# Mainboard33WithHeadersv5.net
KiCad netlist of a schematic drawn in EAGLE
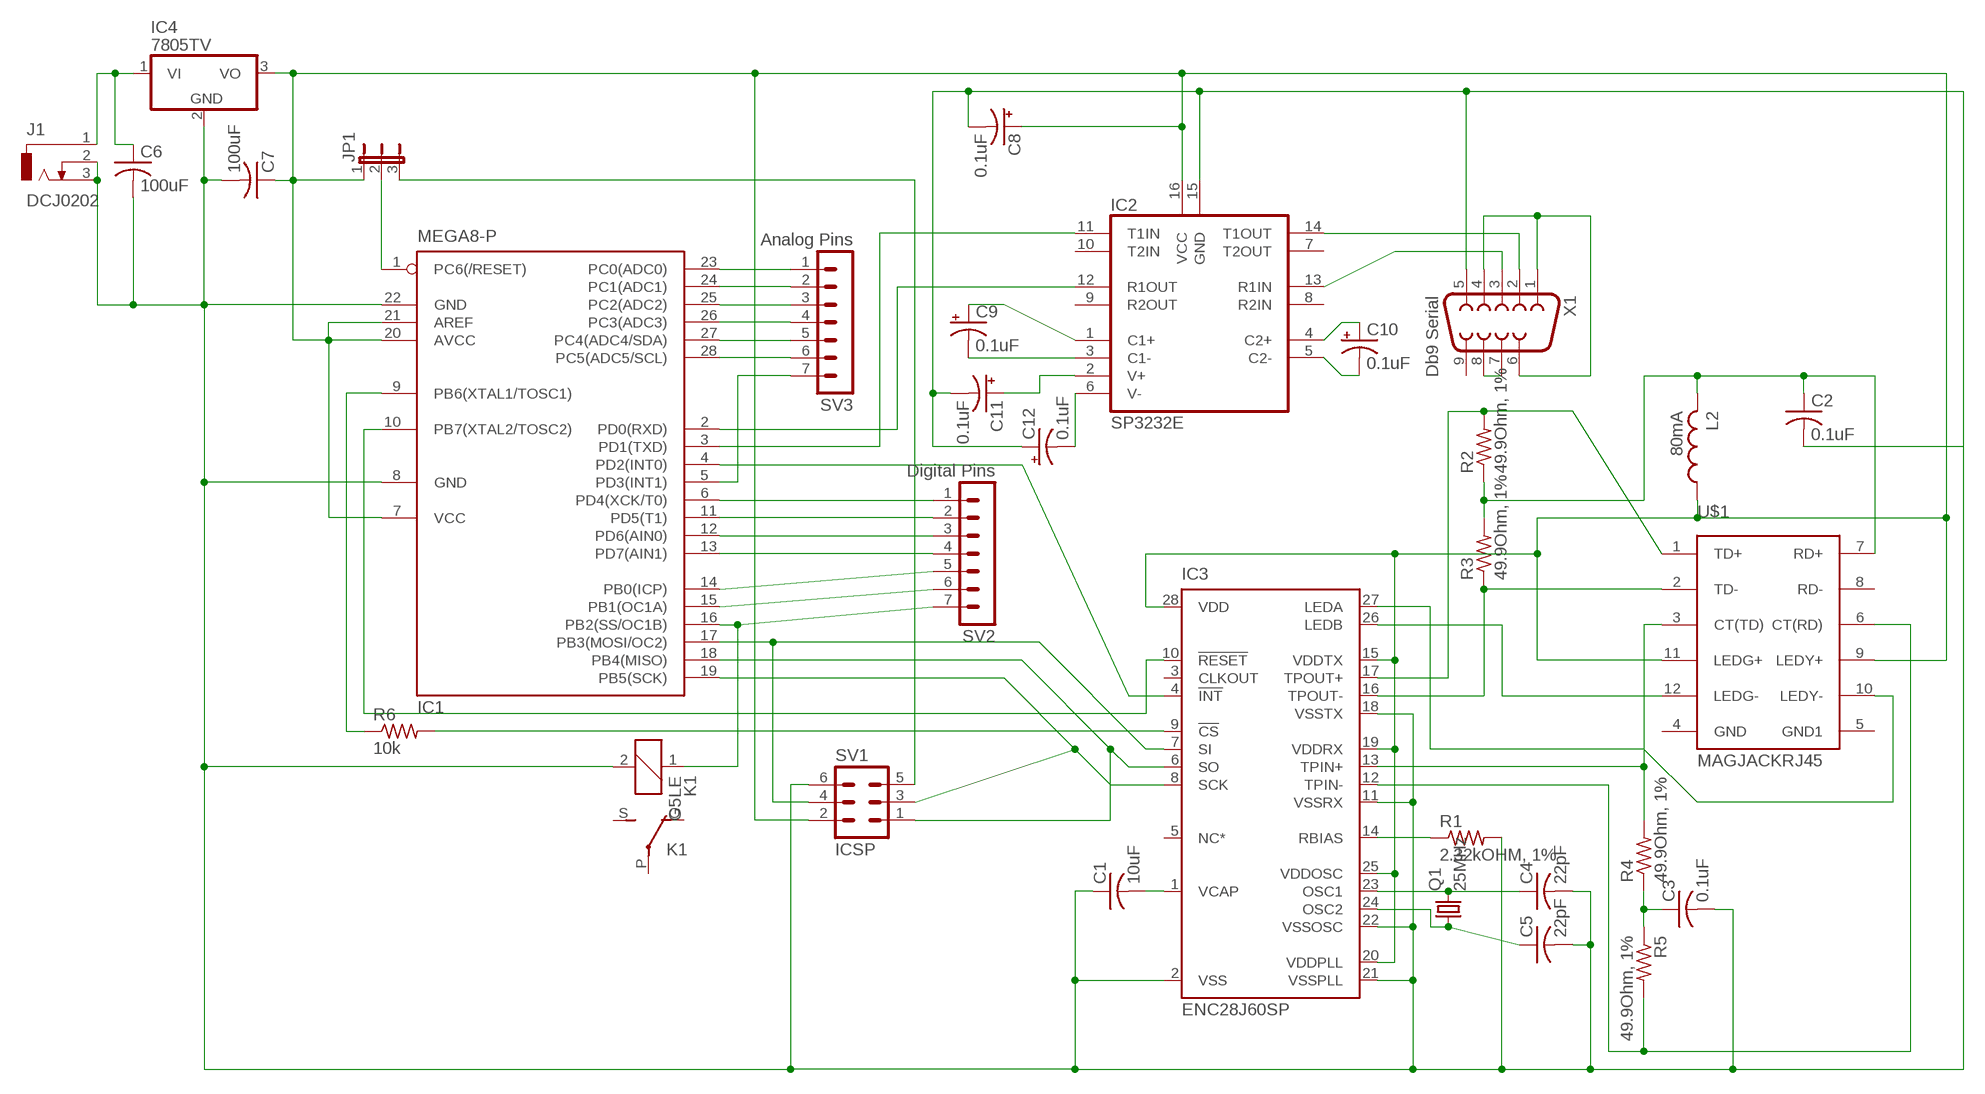
[diagram p0: schematic, sheet 1]

(export (version "E")
  (design (tool "Eeschema 10.0.6"))
  (components
    (comp (ref "C1")
      (value "10uF")
      (footprint "eagle-import:C050-024X044")
      (libsource (lib "eagle-import") (part "C-US050-024X044"))
    )
    (comp (ref "C2")
      (value "0.1uF")
      (footprint "eagle-import:C050-024X044")
      (libsource (lib "eagle-import") (part "C-US050-024X044"))
    )
    (comp (ref "C3")
      (value "0.1uF")
      (footprint "eagle-import:C050-024X044")
      (libsource (lib "eagle-import") (part "C-US050-024X044"))
    )
    (comp (ref "C4")
      (value "22pF")
      (footprint "eagle-import:C050-024X044")
      (libsource (lib "eagle-import") (part "C-US050-024X044"))
    )
    (comp (ref "C5")
      (value "22pF")
      (footprint "eagle-import:C050-024X044")
      (libsource (lib "eagle-import") (part "C-US050-024X044"))
    )
    (comp (ref "C6")
      (value "100uF")
      (footprint "eagle-import:C050-030X075")
      (libsource (lib "eagle-import") (part "C-US050-030X075"))
    )
    (comp (ref "C7")
      (value "100uF")
      (footprint "eagle-import:C050-035X075")
      (libsource (lib "eagle-import") (part "C-US050-035X075"))
    )
    (comp (ref "C8")
      (value "0.1uF")
      (footprint "eagle-import:E1,8-4")
      (libsource (lib "eagle-import") (part "CPOL-USE1.8-4"))
    )
    (comp (ref "C9")
      (value "0.1uF")
      (footprint "eagle-import:E1,8-4")
      (libsource (lib "eagle-import") (part "CPOL-USE1.8-4"))
    )
    (comp (ref "C10")
      (value "0.1uF")
      (footprint "eagle-import:E1,8-4")
      (libsource (lib "eagle-import") (part "CPOL-USE1.8-4"))
    )
    (comp (ref "C11")
      (value "0.1uF")
      (footprint "eagle-import:E1,8-4")
      (libsource (lib "eagle-import") (part "CPOL-USE1.8-4"))
    )
    (comp (ref "C12")
      (value "0.1uF")
      (footprint "eagle-import:E1,8-4")
      (libsource (lib "eagle-import") (part "CPOL-USE1.8-4"))
    )
    (comp (ref "IC1")
      (value "MEGA8-P")
      (footprint "eagle-import:DIL28-3")
      (libsource (lib "eagle-import") (part "MEGA8-P"))
    )
    (comp (ref "IC2")
      (value "SP3232E")
      (footprint "eagle-import:DIL16")
      (libsource (lib "eagle-import") (part "SP3232ESP3232E"))
    )
    (comp (ref "IC3")
      (value "ENC28J60SP")
      (footprint "eagle-import:DIL28-3")
      (fields (field (name "MF") "MICROCHIP") (field (name "MPN") "ENC28J60/SP"))
      (libsource (lib "eagle-import") (part "ENC28J60SP"))
    )
    (comp (ref "IC4")
      (value "7805TV")
      (footprint "eagle-import:TO220V")
      (libsource (lib "eagle-import") (part "78TV05"))
    )
    (comp (ref "J1")
      (value "DCJ0202")
      (footprint "eagle-import:DCJ0202")
      (libsource (lib "eagle-import") (part "DCJ0202"))
    )
    (comp (ref "JP1")
      (value "JP2E")
      (footprint "eagle-import:JP2")
      (libsource (lib "eagle-import") (part "JP2E"))
    )
    (comp (ref "K1")
      (value "G5LE")
      (footprint "eagle-import:G5LE")
      (libsource (lib "eagle-import") (part "G5LE"))
    )
    (comp (ref "L2")
      (value "80mA")
      (footprint "eagle-import:0207_10")
      (libsource (lib "eagle-import") (part "L-US0207/10"))
    )
    (comp (ref "Q1")
      (value "25MHz")
      (footprint "eagle-import:HC49_S")
      (fields (field (name "OC_FARNELL") "1667008"))
      (libsource (lib "eagle-import") (part "CRYSTALHC49S"))
    )
    (comp (ref "R1")
      (value "2.32kOHM, 1%")
      (footprint "eagle-import:0204_5")
      (libsource (lib "eagle-import") (part "resistor_R-US_0204/5"))
    )
    (comp (ref "R2")
      (value "49.9Ohm, 1%")
      (footprint "eagle-import:0204_5")
      (libsource (lib "eagle-import") (part "resistor_R-US_0204/5"))
    )
    (comp (ref "R3")
      (value "49.9Ohm, 1%")
      (footprint "eagle-import:0204_5")
      (libsource (lib "eagle-import") (part "resistor_R-US_0204/5"))
    )
    (comp (ref "R4")
      (value "49.9Ohm, 1%")
      (footprint "eagle-import:0204_5")
      (libsource (lib "eagle-import") (part "resistor_R-US_0204/5"))
    )
    (comp (ref "R5")
      (value "49.9Ohm, 1%")
      (footprint "eagle-import:0204_5")
      (libsource (lib "eagle-import") (part "resistor_R-US_0204/5"))
    )
    (comp (ref "R6")
      (value "10k")
      (footprint "eagle-import:0204_5")
      (libsource (lib "eagle-import") (part "R-US_0204/5"))
    )
    (comp (ref "SV1")
      (value "ICSP")
      (footprint "eagle-import:MA03-2")
      (libsource (lib "eagle-import") (part "MA03-2"))
    )
    (comp (ref "SV2")
      (value "Digital Pins")
      (footprint "eagle-import:MA07-1")
      (libsource (lib "eagle-import") (part "MA07-1"))
    )
    (comp (ref "SV3")
      (value "Analog Pins")
      (footprint "eagle-import:MA07-1")
      (libsource (lib "eagle-import") (part "MA07-1"))
    )
    (comp (ref "U$1")
      (value "MAGJACKRJ45")
      (footprint "eagle-import:MAGJACK")
      (libsource (lib "eagle-import") (part "MAGJACKRJ45"))
    )
    (comp (ref "X1")
      (value "Db9 Serial")
      (footprint "eagle-import:F09H")
      (libsource (lib "eagle-import") (part "F09H"))
    )
  )
  (nets
    (net (code "1") (name "/GND") (class "Default")
      (node (ref "U$1") (pin "4") (pinfunction "GND_4") (pintype "power_in"))
    )
    (net (code "2") (name "/GND1") (class "Default")
      (node (ref "U$1") (pin "5") (pinfunction "GND1_5") (pintype "power_in"))
    )
    (net (code "3") (name "Net-(C3-Pad1)") (class "Default")
      (node (ref "C3") (pin "1") (pinfunction "1_1") (pintype "passive"))
      (node (ref "R4") (pin "1") (pinfunction "1_1") (pintype "passive"))
      (node (ref "R5") (pin "1") (pinfunction "1_1") (pintype "passive"))
    )
    (net (code "4") (name "Net-(IC1-AREF)") (class "Default")
      (node (ref "C7") (pin "1") (pinfunction "1_1") (pintype "passive"))
      (node (ref "C8") (pin "+") (pinfunction "+_+") (pintype "passive"))
      (node (ref "IC1") (pin "20") (pinfunction "AVCC_20") (pintype "power_in"))
      (node (ref "IC1") (pin "21") (pinfunction "AREF_21") (pintype "passive"))
      (node (ref "IC1") (pin "7") (pinfunction "VCC_7") (pintype "power_in"))
      (node (ref "IC2") (pin "16") (pinfunction "VCC_16") (pintype "power_in"))
      (node (ref "IC3") (pin "15") (pinfunction "VDDTX_15") (pintype "input"))
      (node (ref "IC3") (pin "19") (pinfunction "VDDRX_19") (pintype "input"))
      (node (ref "IC3") (pin "20") (pinfunction "VDDPLL_20") (pintype "input"))
      (node (ref "IC3") (pin "25") (pinfunction "VDDOSC_25") (pintype "input"))
      (node (ref "IC3") (pin "28") (pinfunction "VDD_28") (pintype "input"))
      (node (ref "IC4") (pin "3") (pinfunction "VO_3") (pintype "passive"))
      (node (ref "JP1") (pin "1") (pinfunction "1_1") (pintype "passive"))
      (node (ref "L2") (pin "1") (pinfunction "1_1") (pintype "passive"))
      (node (ref "SV1") (pin "2") (pinfunction "2_2") (pintype "passive"))
      (node (ref "U$1") (pin "11") (pinfunction "LEDG+_11") (pintype "bidirectional"))
      (node (ref "U$1") (pin "9") (pinfunction "LEDY+_9") (pintype "bidirectional"))
    )
    (net (code "5") (name "Net-(IC1-PB0(ICP))") (class "Default")
      (node (ref "IC1") (pin "14") (pinfunction "PB0(ICP)_14") (pintype "bidirectional"))
      (node (ref "SV2") (pin "5") (pinfunction "5_5") (pintype "passive"))
    )
    (net (code "6") (name "Net-(IC1-PB1(OC1A))") (class "Default")
      (node (ref "IC1") (pin "15") (pinfunction "PB1(OC1A)_15") (pintype "bidirectional"))
      (node (ref "SV2") (pin "6") (pinfunction "6_6") (pintype "passive"))
    )
    (net (code "7") (name "Net-(IC1-PB2(SS{slash}OC1B))") (class "Default")
      (node (ref "IC1") (pin "16") (pinfunction "PB2(SS/OC1B)_16") (pintype "bidirectional"))
      (node (ref "K1") (pin "1") (pinfunction "1_1") (pintype "passive"))
      (node (ref "SV2") (pin "7") (pinfunction "7_7") (pintype "passive"))
    )
    (net (code "8") (name "Net-(IC1-PB3(MOSI{slash}OC2))") (class "Default")
      (node (ref "IC1") (pin "17") (pinfunction "PB3(MOSI/OC2)_17") (pintype "bidirectional"))
      (node (ref "IC3") (pin "7") (pinfunction "SI_7") (pintype "input"))
      (node (ref "SV1") (pin "4") (pinfunction "4_4") (pintype "passive"))
    )
    (net (code "9") (name "Net-(IC1-PB4(MISO))") (class "Default")
      (node (ref "IC1") (pin "18") (pinfunction "PB4(MISO)_18") (pintype "bidirectional"))
      (node (ref "IC3") (pin "6") (pinfunction "SO_6") (pintype "output"))
      (node (ref "SV1") (pin "1") (pinfunction "1_1") (pintype "passive"))
    )
    (net (code "10") (name "Net-(IC1-PB5(SCK))") (class "Default")
      (node (ref "IC1") (pin "19") (pinfunction "PB5(SCK)_19") (pintype "bidirectional"))
      (node (ref "IC3") (pin "8") (pinfunction "SCK_8") (pintype "input"))
      (node (ref "SV1") (pin "3") (pinfunction "3_3") (pintype "passive"))
    )
    (net (code "11") (name "Net-(IC1-PB6(XTAL1{slash}TOSC1))") (class "Default")
      (node (ref "IC1") (pin "9") (pinfunction "PB6(XTAL1/TOSC1)_9") (pintype "bidirectional"))
      (node (ref "R6") (pin "1") (pinfunction "1_1") (pintype "passive"))
    )
    (net (code "12") (name "Net-(IC1-PB7(XTAL2{slash}TOSC2))") (class "Default")
      (node (ref "IC1") (pin "10") (pinfunction "PB7(XTAL2/TOSC2)_10") (pintype "bidirectional"))
      (node (ref "IC3") (pin "10") (pinfunction "~{RESET}_10") (pintype "input"))
    )
    (net (code "13") (name "Net-(IC1-PC0(ADC0))") (class "Default")
      (node (ref "IC1") (pin "23") (pinfunction "PC0(ADC0)_23") (pintype "bidirectional"))
      (node (ref "SV3") (pin "1") (pinfunction "1_1") (pintype "passive"))
    )
    (net (code "14") (name "Net-(IC1-PC1(ADC1))") (class "Default")
      (node (ref "IC1") (pin "24") (pinfunction "PC1(ADC1)_24") (pintype "bidirectional"))
      (node (ref "SV3") (pin "2") (pinfunction "2_2") (pintype "passive"))
    )
    (net (code "15") (name "Net-(IC1-PC2(ADC2))") (class "Default")
      (node (ref "IC1") (pin "25") (pinfunction "PC2(ADC2)_25") (pintype "bidirectional"))
      (node (ref "SV3") (pin "3") (pinfunction "3_3") (pintype "passive"))
    )
    (net (code "16") (name "Net-(IC1-PC3(ADC3))") (class "Default")
      (node (ref "IC1") (pin "26") (pinfunction "PC3(ADC3)_26") (pintype "bidirectional"))
      (node (ref "SV3") (pin "4") (pinfunction "4_4") (pintype "passive"))
    )
    (net (code "17") (name "Net-(IC1-PC4(ADC4{slash}SDA))") (class "Default")
      (node (ref "IC1") (pin "27") (pinfunction "PC4(ADC4/SDA)_27") (pintype "bidirectional"))
      (node (ref "SV3") (pin "5") (pinfunction "5_5") (pintype "passive"))
    )
    (net (code "18") (name "Net-(IC1-PC5(ADC5{slash}SCL))") (class "Default")
      (node (ref "IC1") (pin "28") (pinfunction "PC5(ADC5/SCL)_28") (pintype "bidirectional"))
      (node (ref "SV3") (pin "6") (pinfunction "6_6") (pintype "passive"))
    )
    (net (code "19") (name "Net-(IC1-PC6({slash}RESET))") (class "Default")
      (node (ref "IC1") (pin "1") (pinfunction "PC6(/RESET)_1") (pintype "bidirectional"))
      (node (ref "JP1") (pin "2") (pinfunction "2_2") (pintype "passive"))
    )
    (net (code "20") (name "Net-(IC1-PD0(RXD))") (class "Default")
      (node (ref "IC1") (pin "2") (pinfunction "PD0(RXD)_2") (pintype "bidirectional"))
      (node (ref "IC2") (pin "12") (pinfunction "R1OUT_12") (pintype "output"))
    )
    (net (code "21") (name "Net-(IC1-PD1(TXD))") (class "Default")
      (node (ref "IC1") (pin "3") (pinfunction "PD1(TXD)_3") (pintype "bidirectional"))
      (node (ref "IC2") (pin "11") (pinfunction "T1IN_11") (pintype "input"))
    )
    (net (code "22") (name "Net-(IC1-PD2(INT0))") (class "Default")
      (node (ref "IC1") (pin "4") (pinfunction "PD2(INT0)_4") (pintype "bidirectional"))
      (node (ref "IC3") (pin "4") (pinfunction "~{INT}_4") (pintype "output"))
    )
    (net (code "23") (name "Net-(IC1-PD3(INT1))") (class "Default")
      (node (ref "IC1") (pin "5") (pinfunction "PD3(INT1)_5") (pintype "bidirectional"))
      (node (ref "SV3") (pin "7") (pinfunction "7_7") (pintype "passive"))
    )
    (net (code "24") (name "Net-(IC1-PD4(XCK{slash}T0))") (class "Default")
      (node (ref "IC1") (pin "6") (pinfunction "PD4(XCK/T0)_6") (pintype "bidirectional"))
      (node (ref "SV2") (pin "1") (pinfunction "1_1") (pintype "passive"))
    )
    (net (code "25") (name "Net-(IC1-PD5(T1))") (class "Default")
      (node (ref "IC1") (pin "11") (pinfunction "PD5(T1)_11") (pintype "bidirectional"))
      (node (ref "SV2") (pin "2") (pinfunction "2_2") (pintype "passive"))
    )
    (net (code "26") (name "Net-(IC1-PD6(AIN0))") (class "Default")
      (node (ref "IC1") (pin "12") (pinfunction "PD6(AIN0)_12") (pintype "bidirectional"))
      (node (ref "SV2") (pin "3") (pinfunction "3_3") (pintype "passive"))
    )
    (net (code "27") (name "Net-(IC1-PD7(AIN1))") (class "Default")
      (node (ref "IC1") (pin "13") (pinfunction "PD7(AIN1)_13") (pintype "bidirectional"))
      (node (ref "SV2") (pin "4") (pinfunction "4_4") (pintype "passive"))
    )
    (net (code "28") (name "Net-(IC2-C1+)") (class "Default")
      (node (ref "C9") (pin "+") (pinfunction "+_+") (pintype "passive"))
      (node (ref "IC2") (pin "1") (pinfunction "C1+_1") (pintype "input"))
    )
    (net (code "29") (name "Net-(IC2-C1-)") (class "Default")
      (node (ref "C9") (pin "-") (pinfunction "-_-") (pintype "passive"))
      (node (ref "IC2") (pin "3") (pinfunction "C1-_3") (pintype "input"))
    )
    (net (code "30") (name "Net-(IC2-C2+)") (class "Default")
      (node (ref "C10") (pin "+") (pinfunction "+_+") (pintype "passive"))
      (node (ref "IC2") (pin "4") (pinfunction "C2+_4") (pintype "input"))
    )
    (net (code "31") (name "Net-(IC2-C2-)") (class "Default")
      (node (ref "C10") (pin "-") (pinfunction "-_-") (pintype "passive"))
      (node (ref "IC2") (pin "5") (pinfunction "C2-_5") (pintype "input"))
    )
    (net (code "32") (name "Net-(IC2-GND)") (class "Default")
      (node (ref "C1") (pin "1") (pinfunction "1_1") (pintype "passive"))
      (node (ref "C11") (pin "-") (pinfunction "-_-") (pintype "passive"))
      (node (ref "C12") (pin "+") (pinfunction "+_+") (pintype "passive"))
      (node (ref "C2") (pin "2") (pinfunction "2_2") (pintype "passive"))
      (node (ref "C3") (pin "2") (pinfunction "2_2") (pintype "passive"))
      (node (ref "C4") (pin "2") (pinfunction "2_2") (pintype "passive"))
      (node (ref "C5") (pin "2") (pinfunction "2_2") (pintype "passive"))
      (node (ref "C6") (pin "2") (pinfunction "2_2") (pintype "passive"))
      (node (ref "C7") (pin "2") (pinfunction "2_2") (pintype "passive"))
      (node (ref "C8") (pin "-") (pinfunction "-_-") (pintype "passive"))
      (node (ref "IC1") (pin "22") (pinfunction "GND_22") (pintype "power_in"))
      (node (ref "IC1") (pin "8") (pinfunction "GND_8") (pintype "power_in"))
      (node (ref "IC2") (pin "15") (pinfunction "GND_15") (pintype "power_in"))
      (node (ref "IC3") (pin "11") (pinfunction "VSSRX_11") (pintype "input"))
      (node (ref "IC3") (pin "18") (pinfunction "VSSTX_18") (pintype "input"))
      (node (ref "IC3") (pin "2") (pinfunction "VSS_2") (pintype "input"))
      (node (ref "IC3") (pin "21") (pinfunction "VSSPLL_21") (pintype "input"))
      (node (ref "IC3") (pin "22") (pinfunction "VSSOSC_22") (pintype "input"))
      (node (ref "IC4") (pin "2") (pinfunction "GND_2") (pintype "passive"))
      (node (ref "J1") (pin "2") (pinfunction "2_2") (pintype "passive"))
      (node (ref "J1") (pin "3") (pinfunction "3_3") (pintype "passive"))
      (node (ref "K1") (pin "2") (pinfunction "2_2") (pintype "passive"))
      (node (ref "R1") (pin "2") (pinfunction "2_2") (pintype "passive"))
      (node (ref "SV1") (pin "6") (pinfunction "6_6") (pintype "passive"))
      (node (ref "X1") (pin "5") (pinfunction "5_5") (pintype "passive"))
    )
    (net (code "33") (name "Net-(IC2-R1IN)") (class "Default")
      (node (ref "IC2") (pin "13") (pinfunction "R1IN_13") (pintype "input"))
      (node (ref "X1") (pin "3") (pinfunction "3_3") (pintype "passive"))
    )
    (net (code "34") (name "Net-(IC2-T1OUT)") (class "Default")
      (node (ref "IC2") (pin "14") (pinfunction "T1OUT_14") (pintype "output"))
      (node (ref "X1") (pin "2") (pinfunction "2_2") (pintype "passive"))
    )
    (net (code "35") (name "Net-(IC2-V+)") (class "Default")
      (node (ref "C11") (pin "+") (pinfunction "+_+") (pintype "passive"))
      (node (ref "IC2") (pin "2") (pinfunction "V+_2") (pintype "input"))
    )
    (net (code "36") (name "Net-(IC2-V-)") (class "Default")
      (node (ref "C12") (pin "-") (pinfunction "-_-") (pintype "passive"))
      (node (ref "IC2") (pin "6") (pinfunction "V-_6") (pintype "input"))
    )
    (net (code "37") (name "Net-(IC3-LEDA)") (class "Default")
      (node (ref "IC3") (pin "27") (pinfunction "LEDA_27") (pintype "output"))
      (node (ref "U$1") (pin "10") (pinfunction "LEDY-_10") (pintype "bidirectional"))
    )
    (net (code "38") (name "Net-(IC3-LEDB)") (class "Default")
      (node (ref "IC3") (pin "26") (pinfunction "LEDB_26") (pintype "output"))
      (node (ref "U$1") (pin "12") (pinfunction "LEDG-_12") (pintype "bidirectional"))
    )
    (net (code "39") (name "Net-(IC3-OSC1)") (class "Default")
      (node (ref "C4") (pin "1") (pinfunction "1_1") (pintype "passive"))
      (node (ref "IC3") (pin "23") (pinfunction "OSC1_23") (pintype "input"))
      (node (ref "Q1") (pin "2") (pinfunction "2_2") (pintype "passive"))
    )
    (net (code "40") (name "Net-(IC3-OSC2)") (class "Default")
      (node (ref "C5") (pin "1") (pinfunction "1_1") (pintype "passive"))
      (node (ref "IC3") (pin "24") (pinfunction "OSC2_24") (pintype "output"))
      (node (ref "Q1") (pin "1") (pinfunction "1_1") (pintype "passive"))
    )
    (net (code "41") (name "Net-(IC3-RBIAS)") (class "Default")
      (node (ref "IC3") (pin "14") (pinfunction "RBIAS_14") (pintype "input"))
      (node (ref "R1") (pin "1") (pinfunction "1_1") (pintype "passive"))
    )
    (net (code "42") (name "Net-(IC3-TPIN+)") (class "Default")
      (node (ref "IC3") (pin "13") (pinfunction "TPIN+_13") (pintype "input"))
      (node (ref "R4") (pin "2") (pinfunction "2_2") (pintype "passive"))
      (node (ref "U$1") (pin "3") (pinfunction "CT(TD)_3") (pintype "bidirectional"))
    )
    (net (code "43") (name "Net-(IC3-TPIN-)") (class "Default")
      (node (ref "IC3") (pin "12") (pinfunction "TPIN-_12") (pintype "input"))
      (node (ref "R5") (pin "2") (pinfunction "2_2") (pintype "passive"))
      (node (ref "U$1") (pin "6") (pinfunction "CT(RD)_6") (pintype "bidirectional"))
    )
    (net (code "44") (name "Net-(IC3-TPOUT+)") (class "Default")
      (node (ref "IC3") (pin "17") (pinfunction "TPOUT+_17") (pintype "output"))
      (node (ref "R2") (pin "2") (pinfunction "2_2") (pintype "passive"))
      (node (ref "U$1") (pin "1") (pinfunction "TD+_1") (pintype "bidirectional"))
    )
    (net (code "45") (name "Net-(IC3-TPOUT-)") (class "Default")
      (node (ref "IC3") (pin "16") (pinfunction "TPOUT-_16") (pintype "output"))
      (node (ref "R3") (pin "1") (pinfunction "1_1") (pintype "passive"))
      (node (ref "U$1") (pin "2") (pinfunction "TD-_2") (pintype "bidirectional"))
    )
    (net (code "46") (name "Net-(IC3-VCAP)") (class "Default")
      (node (ref "C1") (pin "2") (pinfunction "2_2") (pintype "passive"))
      (node (ref "IC3") (pin "1") (pinfunction "VCAP_1") (pintype "input"))
    )
    (net (code "47") (name "Net-(IC3-~{CS})") (class "Default")
      (node (ref "IC3") (pin "9") (pinfunction "~{CS}_9") (pintype "input"))
      (node (ref "R6") (pin "2") (pinfunction "2_2") (pintype "passive"))
    )
    (net (code "48") (name "Net-(IC4-VI)") (class "Default")
      (node (ref "C6") (pin "1") (pinfunction "1_1") (pintype "passive"))
      (node (ref "IC4") (pin "1") (pinfunction "VI_1") (pintype "input"))
      (node (ref "J1") (pin "1") (pinfunction "1_1") (pintype "passive"))
    )
    (net (code "49") (name "Net-(JP1-Pad3)") (class "Default")
      (node (ref "JP1") (pin "3") (pinfunction "3_3") (pintype "passive"))
      (node (ref "SV1") (pin "5") (pinfunction "5_5") (pintype "passive"))
    )
    (net (code "50") (name "Net-(U$1-RD+)") (class "Default")
      (node (ref "C2") (pin "1") (pinfunction "1_1") (pintype "passive"))
      (node (ref "L2") (pin "2") (pinfunction "2_2") (pintype "passive"))
      (node (ref "R2") (pin "1") (pinfunction "1_1") (pintype "passive"))
      (node (ref "R3") (pin "2") (pinfunction "2_2") (pintype "passive"))
      (node (ref "U$1") (pin "7") (pinfunction "RD+_7") (pintype "bidirectional"))
    )
    (net (code "51") (name "Net-(X1-Pad1)") (class "Default")
      (node (ref "X1") (pin "1") (pinfunction "1_1") (pintype "passive"))
      (node (ref "X1") (pin "4") (pinfunction "4_4") (pintype "passive"))
      (node (ref "X1") (pin "6") (pinfunction "6_6") (pintype "passive"))
    )
    (net (code "52") (name "Net-(X1-Pad7)") (class "Default")
      (node (ref "X1") (pin "7") (pinfunction "7_7") (pintype "passive"))
      (node (ref "X1") (pin "8") (pinfunction "8_8") (pintype "passive"))
    )
    (net (code "53") (name "unconnected-(IC2-R2IN-Pad8)") (class "Default")
      (node (ref "IC2") (pin "8") (pinfunction "R2IN_8") (pintype "input"))
    )
    (net (code "54") (name "unconnected-(IC2-R2OUT-Pad9)") (class "Default")
      (node (ref "IC2") (pin "9") (pinfunction "R2OUT_9") (pintype "output"))
    )
    (net (code "55") (name "unconnected-(IC2-T2IN-Pad10)") (class "Default")
      (node (ref "IC2") (pin "10") (pinfunction "T2IN_10") (pintype "input"))
    )
    (net (code "56") (name "unconnected-(IC2-T2OUT-Pad7)") (class "Default")
      (node (ref "IC2") (pin "7") (pinfunction "T2OUT_7") (pintype "output"))
    )
    (net (code "57") (name "unconnected-(IC3-CLKOUT-Pad3)") (class "Default")
      (node (ref "IC3") (pin "3") (pinfunction "CLKOUT_3") (pintype "output"))
    )
    (net (code "58") (name "unconnected-(IC3-NC*-Pad5)") (class "Default")
      (node (ref "IC3") (pin "5") (pinfunction "NC*_5") (pintype "output"))
    )
    (net (code "59") (name "unconnected-(K1-PadO)") (class "Default")
      (node (ref "K1") (pin "O") (pinfunction "O_O") (pintype "passive"))
    )
    (net (code "60") (name "unconnected-(K1-PadP)") (class "Default")
      (node (ref "K1") (pin "P") (pinfunction "P_P") (pintype "passive"))
    )
    (net (code "61") (name "unconnected-(K1-PadS)") (class "Default")
      (node (ref "K1") (pin "S") (pinfunction "S_S") (pintype "passive"))
    )
    (net (code "62") (name "unconnected-(U$1-RD--Pad8)") (class "Default")
      (node (ref "U$1") (pin "8") (pinfunction "RD-_8") (pintype "bidirectional"))
    )
    (net (code "63") (name "unconnected-(X1-Pad9)") (class "Default")
      (node (ref "X1") (pin "9") (pinfunction "9_9") (pintype "passive"))
    )
  )
)
